# LED_ZuTu-7_0.net
KiCad netlist of a schematic drawn in Altium Designer
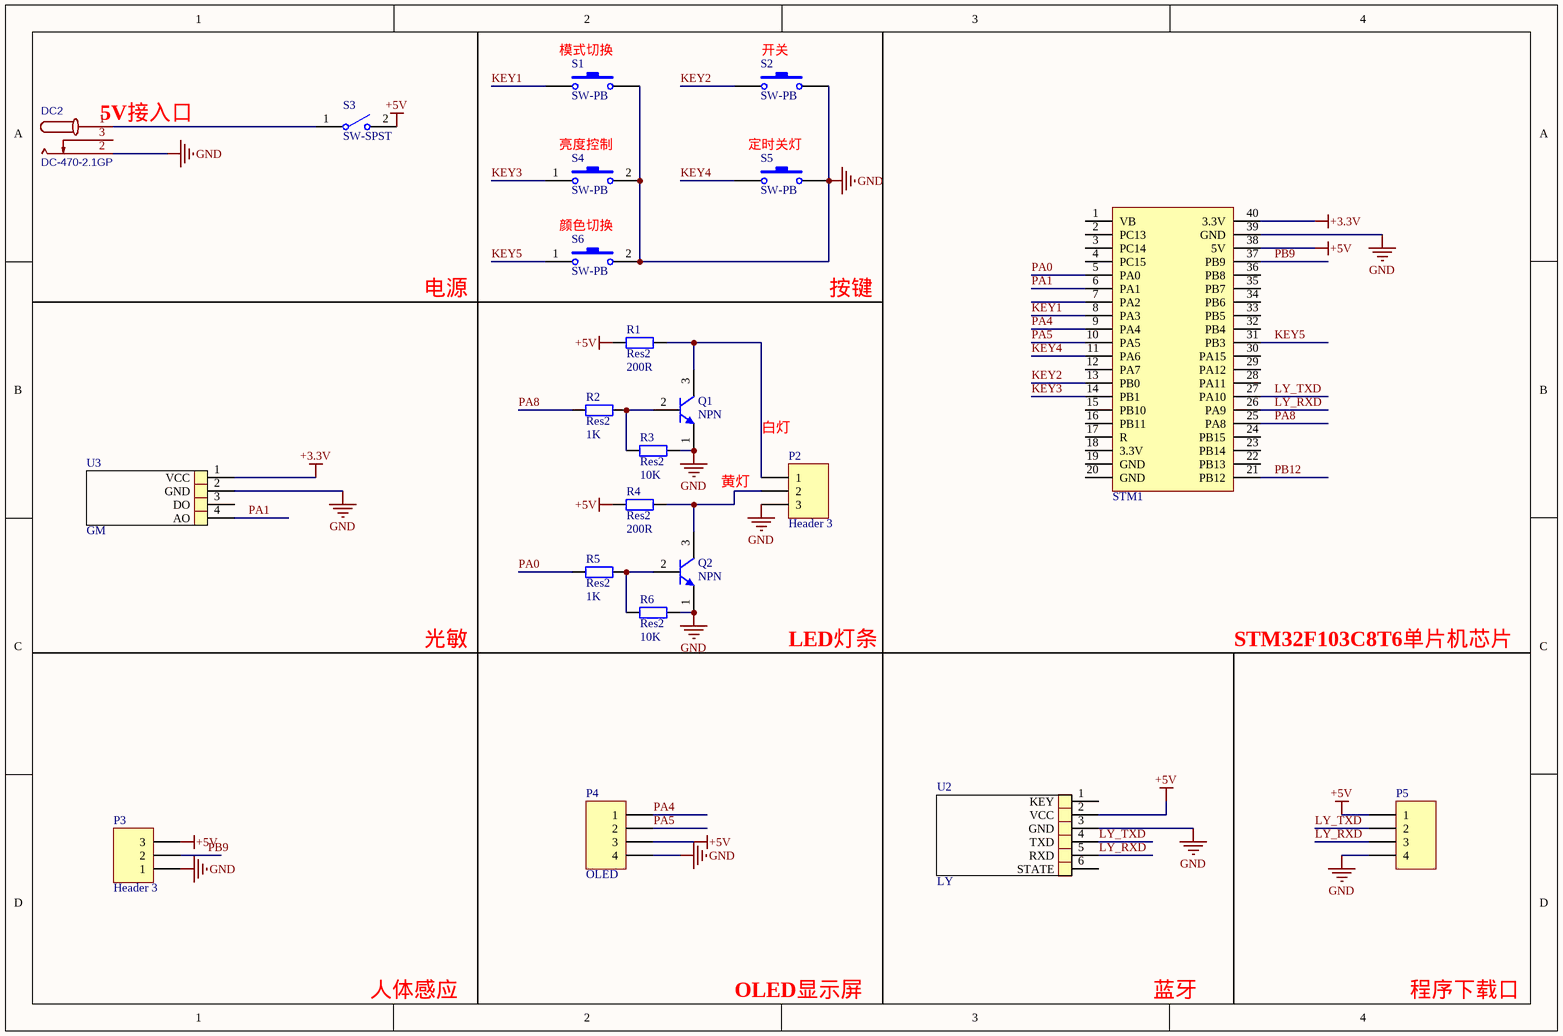
[diagram p0: LED_ZuTu-7.0.SchDoc]

(export (version "E")
  (design (tool "Eeschema 10.0.6"))
  (components
    (comp (ref "DC2")
      (value "DC-470-2.1GP")
      (footprint "Q_J:DC-470-2.1GP - duplicate")
      (fields (field (name "BOM_SUPPLIER PART") "C194407") (field (name "CONTRIBUTOR") "LCSC"))
      (libsource (lib "Q_J") (part "DC-470-2.1GP"))
    )
    (comp (ref "P2")
      (value "Header 3")
      (footprint "HDR1X3")
      (description "Header, 3-Pin")
      (fields (field (name "PUBLISHER") "Altium Limited"))
      (libsource (lib "") (part "Header 3_1"))
    )
    (comp (ref "P3")
      (value "Header 3")
      (footprint "HDR1X3")
      (description "Header, 3-Pin")
      (fields (field (name "PUBLISHER") "Altium Limited"))
      (libsource (lib "Miscellaneous Connectors") (part "Header 3"))
    )
    (comp (ref "P4")
      (value "OLED")
      (footprint "HDR1X4")
      (description "Header, 4-Pin")
      (fields (field (name "PUBLISHER") "Altium Limited"))
      (libsource (lib "Miscellaneous Connectors") (part "Header 4"))
    )
    (comp (ref "P5")
      (value "~")
      (footprint "HDR1X4")
      (description "Header, 4-Pin")
      (fields (field (name "PUBLISHER") "Altium Limited"))
      (libsource (lib "") (part "Header 4_1"))
    )
    (comp (ref "Q1")
      (value "NPN")
      (footprint "Q_J:SOT-23R")
      (description "NPN Bipolar Transistor")
      (fields (field (name "PUBLISHER") "Altium Limited"))
      (libsource (lib "Miscellaneous Devices") (part "NPN"))
    )
    (comp (ref "Q2")
      (value "NPN")
      (footprint "Q_J:SOT-23R")
      (description "NPN Bipolar Transistor")
      (fields (field (name "PUBLISHER") "Altium Limited"))
      (libsource (lib "Miscellaneous Devices") (part "NPN"))
    )
    (comp (ref "R1")
      (value "Res2")
      (footprint "Q_J:0805")
      (description "贴片电阻8050")
      (fields (field (name "ALTIUM_VALUE") "200R") (field (name "PUBLISHER") "Altium Limited"))
      (libsource (lib "Miscellaneous Devices") (part "Res2"))
    )
    (comp (ref "R2")
      (value "Res2")
      (footprint "Q_J:0805")
      (description "贴片电阻8050")
      (fields (field (name "ALTIUM_VALUE") "1K") (field (name "PUBLISHER") "Altium Limited"))
      (libsource (lib "Miscellaneous Devices") (part "Res2"))
    )
    (comp (ref "R3")
      (value "Res2")
      (footprint "Q_J:0805")
      (description "贴片电阻8050")
      (fields (field (name "ALTIUM_VALUE") "10K") (field (name "PUBLISHER") "Altium Limited"))
      (libsource (lib "Miscellaneous Devices") (part "Res2"))
    )
    (comp (ref "R4")
      (value "Res2")
      (footprint "Q_J:0805")
      (description "贴片电阻8050")
      (fields (field (name "ALTIUM_VALUE") "200R") (field (name "PUBLISHER") "Altium Limited"))
      (libsource (lib "Miscellaneous Devices") (part "Res2"))
    )
    (comp (ref "R5")
      (value "Res2")
      (footprint "Q_J:0805")
      (description "贴片电阻8050")
      (fields (field (name "ALTIUM_VALUE") "1K") (field (name "PUBLISHER") "Altium Limited"))
      (libsource (lib "Miscellaneous Devices") (part "Res2"))
    )
    (comp (ref "R6")
      (value "Res2")
      (footprint "Q_J:0805")
      (description "贴片电阻8050")
      (fields (field (name "ALTIUM_VALUE") "10K") (field (name "PUBLISHER") "Altium Limited"))
      (libsource (lib "Miscellaneous Devices") (part "Res2"))
    )
    (comp (ref "S1")
      (value "SW-PB")
      (footprint "Q_J:KEY_M")
      (description "Switch")
      (fields (field (name "PUBLISHER") "Altium Limited"))
      (libsource (lib "Miscellaneous Devices") (part "SW-PB"))
    )
    (comp (ref "S2")
      (value "SW-PB")
      (footprint "Q_J:KEY_M")
      (description "Switch")
      (fields (field (name "PUBLISHER") "Altium Limited"))
      (libsource (lib "Miscellaneous Devices") (part "SW-PB"))
    )
    (comp (ref "S3")
      (value "SW-SPST")
      (footprint "Q_J:BTN8.5*8.5")
      (description "Single-Pole, Single-Throw Switch")
      (fields (field (name "PUBLISHER") "Altium Limited"))
      (libsource (lib "Miscellaneous Devices") (part "SW-SPST"))
    )
    (comp (ref "S4")
      (value "SW-PB")
      (footprint "Q_J:KEY_M")
      (description "Switch")
      (fields (field (name "PUBLISHER") "Altium Limited"))
      (libsource (lib "") (part "SW-PB_1"))
    )
    (comp (ref "S5")
      (value "SW-PB")
      (footprint "Q_J:KEY_M")
      (description "Switch")
      (fields (field (name "PUBLISHER") "Altium Limited"))
      (libsource (lib "Miscellaneous Devices") (part "SW-PB"))
    )
    (comp (ref "S6")
      (value "SW-PB")
      (footprint "Q_J:KEY_M")
      (description "Switch")
      (fields (field (name "PUBLISHER") "Altium Limited"))
      (libsource (lib "") (part "SW-PB_1"))
    )
    (comp (ref "STM1")
      (value "stm32f103c8t6_Board")
      (footprint "stm32-port")
      (description "MCU")
      (libsource (lib "Q_J") (part "stm32f103c8t6_Board"))
    )
    (comp (ref "U2") (value "LY") (footprint "HDR1X6") (libsource (lib "Q_J") (part "LY")))
    (comp (ref "U3") (value "GM") (footprint "HDR1X4") (libsource (lib "Q_J") (part "GM")))
  )
  (nets
    (net (code "1") (name "+3.3V") (class "Default")
      (node (ref "STM1") (pin "40") (pinfunction "3.3V_40") (pintype "passive"))
      (node (ref "U3") (pin "1") (pinfunction "VCC_1") (pintype "passive"))
    )
    (net (code "2") (name "+5V") (class "Default")
      (node (ref "P3") (pin "3") (pinfunction "3_3") (pintype "passive"))
      (node (ref "P4") (pin "3") (pinfunction "3_3") (pintype "passive"))
      (node (ref "P5") (pin "1") (pinfunction "1_1") (pintype "passive"))
      (node (ref "R1") (pin "1") (pinfunction "1_1") (pintype "passive"))
      (node (ref "R4") (pin "1") (pinfunction "1_1") (pintype "passive"))
      (node (ref "S3") (pin "2") (pinfunction "NO_2") (pintype "passive"))
      (node (ref "STM1") (pin "38") (pinfunction "5V_38") (pintype "passive"))
      (node (ref "U2") (pin "2") (pinfunction "VCC_2") (pintype "passive"))
    )
    (net (code "3") (name "/KEY1") (class "Default")
      (node (ref "S1") (pin "1") (pinfunction "1_1") (pintype "passive"))
      (node (ref "STM1") (pin "8") (pinfunction "PA3_8") (pintype "passive"))
    )
    (net (code "4") (name "/KEY2") (class "Default")
      (node (ref "S2") (pin "1") (pinfunction "1_1") (pintype "passive"))
      (node (ref "STM1") (pin "13") (pinfunction "PB0_13") (pintype "passive"))
    )
    (net (code "5") (name "/KEY3") (class "Default")
      (node (ref "S4") (pin "1") (pinfunction "1_1") (pintype "passive"))
      (node (ref "STM1") (pin "14") (pinfunction "PB1_14") (pintype "passive"))
    )
    (net (code "6") (name "/KEY4") (class "Default")
      (node (ref "S5") (pin "1") (pinfunction "1_1") (pintype "passive"))
      (node (ref "STM1") (pin "11") (pinfunction "PA6_11") (pintype "passive"))
    )
    (net (code "7") (name "/KEY5") (class "Default")
      (node (ref "S6") (pin "1") (pinfunction "1_1") (pintype "passive"))
      (node (ref "STM1") (pin "31") (pinfunction "PB3_31") (pintype "passive"))
    )
    (net (code "8") (name "/LY_RXD") (class "Default")
      (node (ref "P5") (pin "3") (pinfunction "3_3") (pintype "passive"))
      (node (ref "STM1") (pin "26") (pinfunction "PA9_26") (pintype "passive"))
      (node (ref "U2") (pin "5") (pinfunction "RXD_5") (pintype "passive"))
    )
    (net (code "9") (name "/LY_TXD") (class "Default")
      (node (ref "P5") (pin "2") (pinfunction "2_2") (pintype "passive"))
      (node (ref "STM1") (pin "27") (pinfunction "PA10_27") (pintype "passive"))
      (node (ref "U2") (pin "4") (pinfunction "TXD_4") (pintype "passive"))
    )
    (net (code "10") (name "/PA0") (class "Default")
      (node (ref "R5") (pin "1") (pinfunction "1_1") (pintype "passive"))
      (node (ref "STM1") (pin "5") (pinfunction "PA0_5") (pintype "passive"))
    )
    (net (code "11") (name "/PA1") (class "Default")
      (node (ref "STM1") (pin "6") (pinfunction "PA1_6") (pintype "passive"))
      (node (ref "U3") (pin "4") (pinfunction "AO_4") (pintype "passive"))
    )
    (net (code "12") (name "/PA4") (class "Default")
      (node (ref "P4") (pin "1") (pinfunction "1_1") (pintype "passive"))
      (node (ref "STM1") (pin "9") (pinfunction "PA4_9") (pintype "passive"))
    )
    (net (code "13") (name "/PA5") (class "Default")
      (node (ref "P4") (pin "2") (pinfunction "2_2") (pintype "passive"))
      (node (ref "STM1") (pin "10") (pinfunction "PA5_10") (pintype "passive"))
    )
    (net (code "14") (name "/PA8") (class "Default")
      (node (ref "R2") (pin "1") (pinfunction "1_1") (pintype "passive"))
      (node (ref "STM1") (pin "25") (pinfunction "PA8_25") (pintype "passive"))
    )
    (net (code "15") (name "/PB9") (class "Default")
      (node (ref "P3") (pin "2") (pinfunction "2_2") (pintype "passive"))
      (node (ref "STM1") (pin "37") (pinfunction "PB9_37") (pintype "passive"))
    )
    (net (code "16") (name "/PB12") (class "Default")
      (node (ref "STM1") (pin "21") (pinfunction "PB12_21") (pintype "passive"))
    )
    (net (code "17") (name "GND") (class "Default")
      (node (ref "DC2") (pin "2") (pinfunction "2_2") (pintype "passive"))
      (node (ref "P2") (pin "3") (pinfunction "3_3") (pintype "passive"))
      (node (ref "P3") (pin "1") (pinfunction "1_1") (pintype "passive"))
      (node (ref "P4") (pin "4") (pinfunction "4_4") (pintype "passive"))
      (node (ref "P5") (pin "4") (pinfunction "4_4") (pintype "passive"))
      (node (ref "Q1") (pin "1") (pinfunction "E_1") (pintype "passive"))
      (node (ref "Q2") (pin "1") (pinfunction "E_1") (pintype "passive"))
      (node (ref "R3") (pin "2") (pinfunction "2_2") (pintype "passive"))
      (node (ref "R6") (pin "2") (pinfunction "2_2") (pintype "passive"))
      (node (ref "S1") (pin "2") (pinfunction "2_2") (pintype "passive"))
      (node (ref "S2") (pin "2") (pinfunction "2_2") (pintype "passive"))
      (node (ref "S4") (pin "2") (pinfunction "2_2") (pintype "passive"))
      (node (ref "S5") (pin "2") (pinfunction "2_2") (pintype "passive"))
      (node (ref "S6") (pin "2") (pinfunction "2_2") (pintype "passive"))
      (node (ref "STM1") (pin "39") (pinfunction "GND_39") (pintype "passive"))
      (node (ref "U2") (pin "3") (pinfunction "GND_3") (pintype "passive"))
      (node (ref "U3") (pin "2") (pinfunction "GND_2") (pintype "passive"))
    )
    (net (code "18") (name "Net-(Q1-B)") (class "Default")
      (node (ref "Q1") (pin "2") (pinfunction "B_2") (pintype "passive"))
      (node (ref "R2") (pin "2") (pinfunction "2_2") (pintype "passive"))
      (node (ref "R3") (pin "1") (pinfunction "1_1") (pintype "passive"))
    )
    (net (code "19") (name "Net-(Q1-C)") (class "Default")
      (node (ref "P2") (pin "1") (pinfunction "1_1") (pintype "passive"))
      (node (ref "Q1") (pin "3") (pinfunction "C_3") (pintype "passive"))
      (node (ref "R1") (pin "2") (pinfunction "2_2") (pintype "passive"))
    )
    (net (code "20") (name "Net-(Q2-B)") (class "Default")
      (node (ref "Q2") (pin "2") (pinfunction "B_2") (pintype "passive"))
      (node (ref "R5") (pin "2") (pinfunction "2_2") (pintype "passive"))
      (node (ref "R6") (pin "1") (pinfunction "1_1") (pintype "passive"))
    )
    (net (code "21") (name "Net-(Q2-C)") (class "Default")
      (node (ref "P2") (pin "2") (pinfunction "2_2") (pintype "passive"))
      (node (ref "Q2") (pin "3") (pinfunction "C_3") (pintype "passive"))
      (node (ref "R4") (pin "2") (pinfunction "2_2") (pintype "passive"))
    )
    (net (code "22") (name "Net-(S3-COMMON)") (class "Default")
      (node (ref "DC2") (pin "1") (pinfunction "1_1") (pintype "passive"))
      (node (ref "S3") (pin "1") (pinfunction "COMMON_1") (pintype "passive"))
    )
    (net (code "23") (name "unconnected-(DC2-Pad3)") (class "Default")
      (node (ref "DC2") (pin "3") (pinfunction "3_3") (pintype "passive"))
    )
    (net (code "24") (name "unconnected-(STM1-3.3V-Pad18)") (class "Default")
      (node (ref "STM1") (pin "18") (pinfunction "3.3V_18") (pintype "passive"))
    )
    (net (code "25") (name "unconnected-(STM1-GND-Pad19)") (class "Default")
      (node (ref "STM1") (pin "19") (pinfunction "GND_19") (pintype "passive"))
    )
    (net (code "26") (name "unconnected-(STM1-GND-Pad20)") (class "Default")
      (node (ref "STM1") (pin "20") (pinfunction "GND_20") (pintype "passive"))
    )
    (net (code "27") (name "unconnected-(STM1-PA2-Pad7)") (class "Default")
      (node (ref "STM1") (pin "7") (pinfunction "PA2_7") (pintype "passive"))
    )
    (net (code "28") (name "unconnected-(STM1-PA7-Pad12)") (class "Default")
      (node (ref "STM1") (pin "12") (pinfunction "PA7_12") (pintype "passive"))
    )
    (net (code "29") (name "unconnected-(STM1-PA11-Pad28)") (class "Default")
      (node (ref "STM1") (pin "28") (pinfunction "PA11_28") (pintype "passive"))
    )
    (net (code "30") (name "unconnected-(STM1-PA12-Pad29)") (class "Default")
      (node (ref "STM1") (pin "29") (pinfunction "PA12_29") (pintype "passive"))
    )
    (net (code "31") (name "unconnected-(STM1-PA15-Pad30)") (class "Default")
      (node (ref "STM1") (pin "30") (pinfunction "PA15_30") (pintype "passive"))
    )
    (net (code "32") (name "unconnected-(STM1-PB4-Pad32)") (class "Default")
      (node (ref "STM1") (pin "32") (pinfunction "PB4_32") (pintype "passive"))
    )
    (net (code "33") (name "unconnected-(STM1-PB5-Pad33)") (class "Default")
      (node (ref "STM1") (pin "33") (pinfunction "PB5_33") (pintype "passive"))
    )
    (net (code "34") (name "unconnected-(STM1-PB6-Pad34)") (class "Default")
      (node (ref "STM1") (pin "34") (pinfunction "PB6_34") (pintype "passive"))
    )
    (net (code "35") (name "unconnected-(STM1-PB7-Pad35)") (class "Default")
      (node (ref "STM1") (pin "35") (pinfunction "PB7_35") (pintype "passive"))
    )
    (net (code "36") (name "unconnected-(STM1-PB8-Pad36)") (class "Default")
      (node (ref "STM1") (pin "36") (pinfunction "PB8_36") (pintype "passive"))
    )
    (net (code "37") (name "unconnected-(STM1-PB10-Pad15)") (class "Default")
      (node (ref "STM1") (pin "15") (pinfunction "PB10_15") (pintype "passive"))
    )
    (net (code "38") (name "unconnected-(STM1-PB11-Pad16)") (class "Default")
      (node (ref "STM1") (pin "16") (pinfunction "PB11_16") (pintype "passive"))
    )
    (net (code "39") (name "unconnected-(STM1-PB13-Pad22)") (class "Default")
      (node (ref "STM1") (pin "22") (pinfunction "PB13_22") (pintype "passive"))
    )
    (net (code "40") (name "unconnected-(STM1-PB14-Pad23)") (class "Default")
      (node (ref "STM1") (pin "23") (pinfunction "PB14_23") (pintype "passive"))
    )
    (net (code "41") (name "unconnected-(STM1-PB15-Pad24)") (class "Default")
      (node (ref "STM1") (pin "24") (pinfunction "PB15_24") (pintype "passive"))
    )
    (net (code "42") (name "unconnected-(STM1-PC13-Pad2)") (class "Default")
      (node (ref "STM1") (pin "2") (pinfunction "PC13_2") (pintype "passive"))
    )
    (net (code "43") (name "unconnected-(STM1-PC14-Pad3)") (class "Default")
      (node (ref "STM1") (pin "3") (pinfunction "PC14_3") (pintype "passive"))
    )
    (net (code "44") (name "unconnected-(STM1-PC15-Pad4)") (class "Default")
      (node (ref "STM1") (pin "4") (pinfunction "PC15_4") (pintype "passive"))
    )
    (net (code "45") (name "unconnected-(STM1-R-Pad17)") (class "Default")
      (node (ref "STM1") (pin "17") (pinfunction "R_17") (pintype "passive"))
    )
    (net (code "46") (name "unconnected-(STM1-VB-Pad1)") (class "Default")
      (node (ref "STM1") (pin "1") (pinfunction "VB_1") (pintype "passive"))
    )
    (net (code "47") (name "unconnected-(U2-KEY-Pad1)") (class "Default")
      (node (ref "U2") (pin "1") (pinfunction "KEY_1") (pintype "passive"))
    )
    (net (code "48") (name "unconnected-(U2-STATE-Pad6)") (class "Default")
      (node (ref "U2") (pin "6") (pinfunction "STATE_6") (pintype "passive"))
    )
    (net (code "49") (name "unconnected-(U3-DO-Pad3)") (class "Default")
      (node (ref "U3") (pin "3") (pinfunction "DO_3") (pintype "passive"))
    )
  )
)
